# ReadHat_V1_0_0_0.net
KiCad netlist of a schematic drawn in Altium Designer
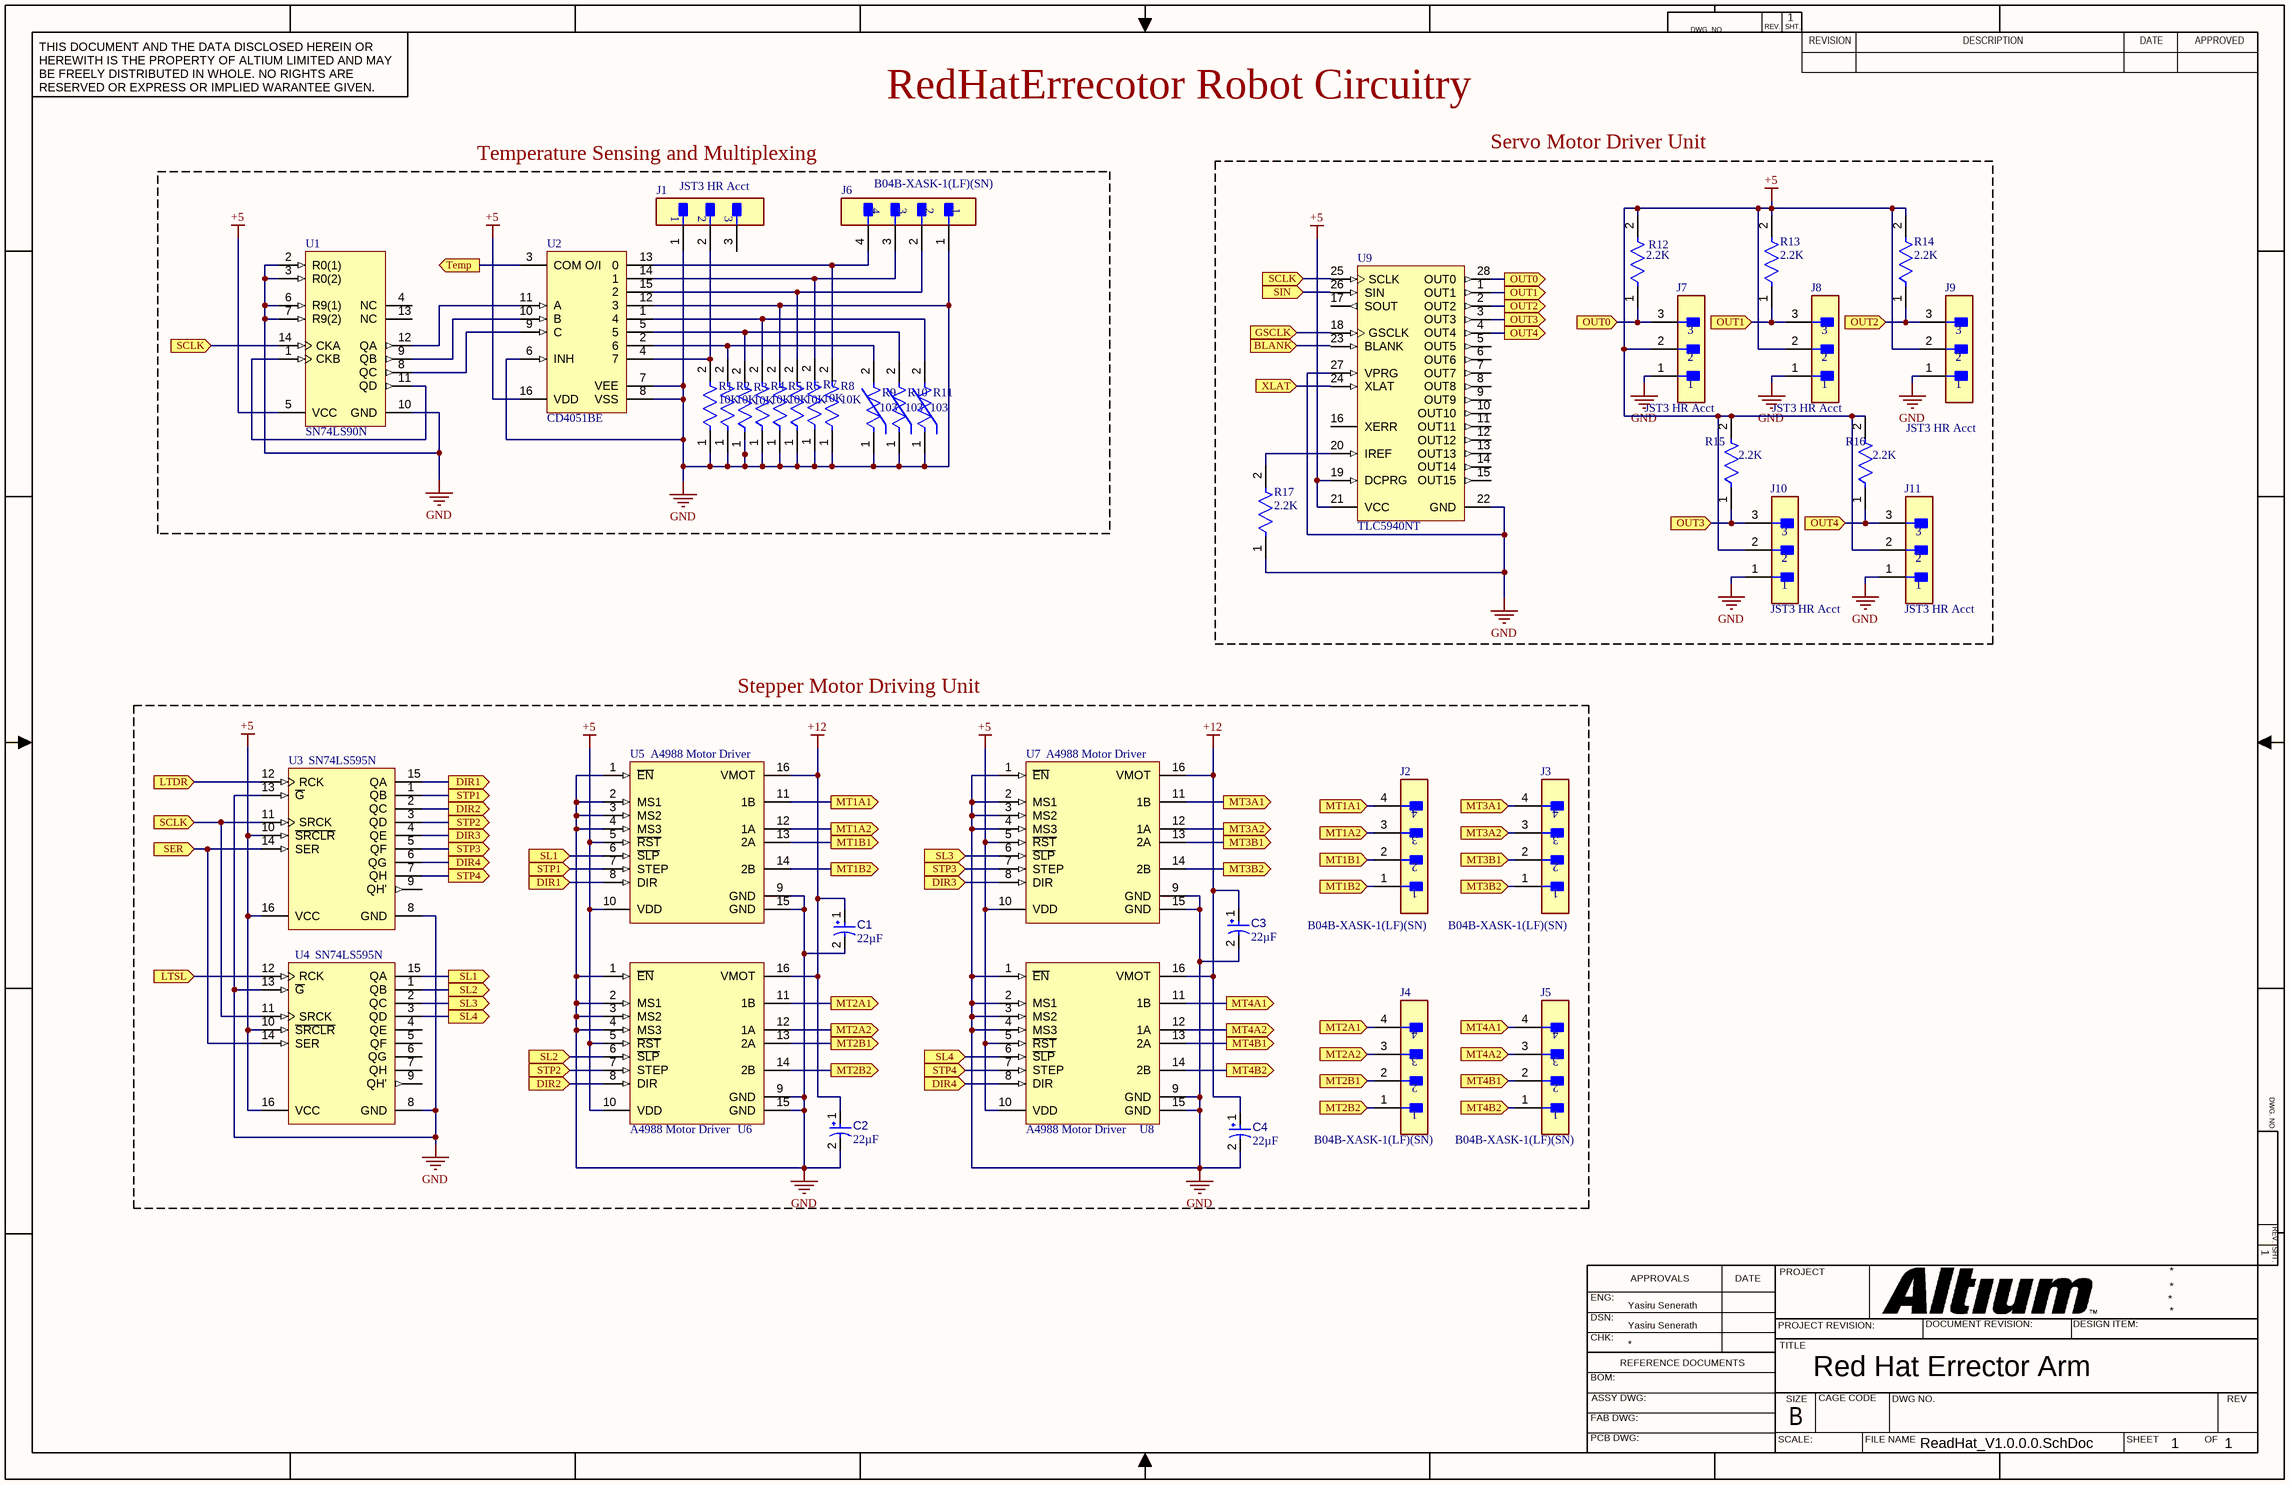
[diagram p0: ReadHat_V1.0.0.0.SchDoc]

(export (version "E")
  (design (tool "Eeschema 10.0.6"))
  (components
    (comp (ref "C1")
      (value "22µF")
      (footprint "CAPPR55-200-1100X500X1200")
      (description "Aluminum Electrolytic Capacitor, 22 uF, +/- 20%, 50 V, -40 to 85 degC, 2-Pin THD, RoHS, Bulk")
      (fields (field (name "MANUFACTURER") "Panasonic") (field (name "TOLERANCE") "20%"))
      (libsource (lib "University of Moratuwa") (part "CAP-P-2"))
    )
    (comp (ref "C2")
      (value "22µF")
      (footprint "CAPPR55-200-1100X500X1200")
      (description "Aluminum Electrolytic Capacitor, 22 uF, +/- 20%, 50 V, -40 to 85 degC, 2-Pin THD, RoHS, Bulk")
      (fields (field (name "MANUFACTURER") "Panasonic") (field (name "TOLERANCE") "20%"))
      (libsource (lib "University of Moratuwa") (part "CAP-P-2"))
    )
    (comp (ref "C3")
      (value "22µF")
      (footprint "CAPPR55-200-1100X500X1200")
      (description "Aluminum Electrolytic Capacitor, 22 uF, +/- 20%, 50 V, -40 to 85 degC, 2-Pin THD, RoHS, Bulk")
      (fields (field (name "MANUFACTURER") "Panasonic") (field (name "TOLERANCE") "20%"))
      (libsource (lib "University of Moratuwa") (part "CAP-P-2"))
    )
    (comp (ref "C4")
      (value "22µF")
      (footprint "CAPPR55-200-1100X500X1200")
      (description "Aluminum Electrolytic Capacitor, 22 uF, +/- 20%, 50 V, -40 to 85 degC, 2-Pin THD, RoHS, Bulk")
      (fields (field (name "MANUFACTURER") "Panasonic") (field (name "TOLERANCE") "20%"))
      (libsource (lib "University of Moratuwa") (part "CAP-P-2"))
    )
    (comp (ref "J1")
      (value "JST3 HR Acct")
      (footprint "FP-B3B-XH-A_LF_SN-MFG")
      (description "CONN HEADER VERT 3POS 2.5MM")
      (libsource (lib "Altium Content Vault") (part "0d3f023dd272f625e17a2be33dea85f"))
    )
    (comp (ref "J2")
      (value "B04B-XASK-1(LF)(SN)")
      (footprint "FP-B04B-XASK-1_LF_SN-MFG")
      (description "CONN HEADER VERT 4POS 2.5MM")
      (fields
        (field (name "OCTOPART") "https://octopart.com/b04b-xask-1%28lf%29%28sn%29-jst-3990149")
        (field (name "MANUFACTURER") "JST")
      )
      (libsource (lib "Altium Content Vault") (part "299a8cea1bdcbc3624fe62c390fa72c"))
    )
    (comp (ref "J3")
      (value "B04B-XASK-1(LF)(SN)")
      (footprint "FP-B04B-XASK-1_LF_SN-MFG")
      (description "CONN HEADER VERT 4POS 2.5MM")
      (fields
        (field (name "OCTOPART") "https://octopart.com/b04b-xask-1%28lf%29%28sn%29-jst-3990149")
        (field (name "MANUFACTURER") "JST")
      )
      (libsource (lib "Altium Content Vault") (part "299a8cea1bdcbc3624fe62c390fa72c"))
    )
    (comp (ref "J4")
      (value "B04B-XASK-1(LF)(SN)")
      (footprint "FP-B04B-XASK-1_LF_SN-MFG")
      (description "CONN HEADER VERT 4POS 2.5MM")
      (fields
        (field (name "OCTOPART") "https://octopart.com/b04b-xask-1%28lf%29%28sn%29-jst-3990149")
        (field (name "MANUFACTURER") "JST")
      )
      (libsource (lib "Altium Content Vault") (part "299a8cea1bdcbc3624fe62c390fa72c"))
    )
    (comp (ref "J5")
      (value "B04B-XASK-1(LF)(SN)")
      (footprint "FP-B04B-XASK-1_LF_SN-MFG")
      (description "CONN HEADER VERT 4POS 2.5MM")
      (fields
        (field (name "OCTOPART") "https://octopart.com/b04b-xask-1%28lf%29%28sn%29-jst-3990149")
        (field (name "MANUFACTURER") "JST")
      )
      (libsource (lib "Altium Content Vault") (part "299a8cea1bdcbc3624fe62c390fa72c"))
    )
    (comp (ref "J6")
      (value "B04B-XASK-1(LF)(SN)")
      (footprint "FP-B04B-XASK-1_LF_SN-MFG")
      (description "CONN HEADER VERT 4POS 2.5MM")
      (fields
        (field (name "OCTOPART") "https://octopart.com/b04b-xask-1%28lf%29%28sn%29-jst-3990149")
        (field (name "MANUFACTURER") "JST")
      )
      (libsource (lib "") (part "299a8cea1bdcbc3624fe62c390fa72c_1"))
    )
    (comp (ref "J7")
      (value "JST3 HR Acct")
      (footprint "FP-B3B-XH-A_LF_SN-MFG")
      (description "CONN HEADER VERT 3POS 2.5MM")
      (libsource (lib "Altium Content Vault") (part "0d3f023dd272f625e17a2be33dea85f"))
    )
    (comp (ref "J8")
      (value "JST3 HR Acct")
      (footprint "FP-B3B-XH-A_LF_SN-MFG")
      (description "CONN HEADER VERT 3POS 2.5MM")
      (libsource (lib "Altium Content Vault") (part "0d3f023dd272f625e17a2be33dea85f"))
    )
    (comp (ref "J9")
      (value "JST3 HR Acct")
      (footprint "FP-B3B-XH-A_LF_SN-MFG")
      (description "CONN HEADER VERT 3POS 2.5MM")
      (libsource (lib "Altium Content Vault") (part "0d3f023dd272f625e17a2be33dea85f"))
    )
    (comp (ref "J10")
      (value "JST3 HR Acct")
      (footprint "FP-B3B-XH-A_LF_SN-MFG")
      (description "CONN HEADER VERT 3POS 2.5MM")
      (libsource (lib "Altium Content Vault") (part "0d3f023dd272f625e17a2be33dea85f"))
    )
    (comp (ref "J11")
      (value "JST3 HR Acct")
      (footprint "FP-B3B-XH-A_LF_SN-MFG")
      (description "CONN HEADER VERT 3POS 2.5MM")
      (libsource (lib "Altium Content Vault") (part "0d3f023dd272f625e17a2be33dea85f"))
    )
    (comp (ref "R1")
      (value "10K")
      (footprint "FP-RNC55-MFG")
      (description "RES 10K OHM 1/8W 1% AXIAL")
      (fields (field (name "TOLERANCE") "1%") (field (name "MANUFACTURER PART NUMBER") "RNC55H1002FSB14"))
      (libsource (lib "Altium Content Vault") (part "1029c3af85768c4190bb7ad29bc67b5"))
    )
    (comp (ref "R2")
      (value "10K")
      (footprint "FP-RNC55-MFG")
      (description "RES 10K OHM 1/8W 1% AXIAL")
      (fields (field (name "TOLERANCE") "1%") (field (name "MANUFACTURER PART NUMBER") "RNC55H1002FSB14"))
      (libsource (lib "Altium Content Vault") (part "1029c3af85768c4190bb7ad29bc67b5"))
    )
    (comp (ref "R3")
      (value "10K")
      (footprint "FP-RNC55-MFG")
      (description "RES 10K OHM 1/8W 1% AXIAL")
      (fields (field (name "TOLERANCE") "1%") (field (name "MANUFACTURER PART NUMBER") "RNC55H1002FSB14"))
      (libsource (lib "Altium Content Vault") (part "1029c3af85768c4190bb7ad29bc67b5"))
    )
    (comp (ref "R4")
      (value "10K")
      (footprint "FP-RNC55-MFG")
      (description "RES 10K OHM 1/8W 1% AXIAL")
      (fields (field (name "TOLERANCE") "1%") (field (name "MANUFACTURER PART NUMBER") "RNC55H1002FSB14"))
      (libsource (lib "Altium Content Vault") (part "1029c3af85768c4190bb7ad29bc67b5"))
    )
    (comp (ref "R5")
      (value "10K")
      (footprint "FP-RNC55-MFG")
      (description "RES 10K OHM 1/8W 1% AXIAL")
      (fields (field (name "TOLERANCE") "1%") (field (name "MANUFACTURER PART NUMBER") "RNC55H1002FSB14"))
      (libsource (lib "Altium Content Vault") (part "1029c3af85768c4190bb7ad29bc67b5"))
    )
    (comp (ref "R6")
      (value "10K")
      (footprint "FP-RNC55-MFG")
      (description "RES 10K OHM 1/8W 1% AXIAL")
      (fields (field (name "TOLERANCE") "1%") (field (name "MANUFACTURER PART NUMBER") "RNC55H1002FSB14"))
      (libsource (lib "Altium Content Vault") (part "1029c3af85768c4190bb7ad29bc67b5"))
    )
    (comp (ref "R7")
      (value "10K")
      (footprint "FP-RNC55-MFG")
      (description "RES 10K OHM 1/8W 1% AXIAL")
      (fields (field (name "TOLERANCE") "1%") (field (name "MANUFACTURER PART NUMBER") "RNC55H1002FSB14"))
      (libsource (lib "Altium Content Vault") (part "1029c3af85768c4190bb7ad29bc67b5"))
    )
    (comp (ref "R8")
      (value "10K")
      (footprint "FP-RNC55-MFG")
      (description "RES 10K OHM 1/8W 1% AXIAL")
      (fields (field (name "TOLERANCE") "1%") (field (name "MANUFACTURER PART NUMBER") "RNC55H1002FSB14"))
      (libsource (lib "Altium Content Vault") (part "1029c3af85768c4190bb7ad29bc67b5"))
    )
    (comp (ref "R9")
      (value "103")
      (footprint "FP-PTFL04_2N34-MFG")
      (description "THERMISTOR PTC 100 OHM DISC")
      (fields (field (name "VOLTAGE") "16V"))
      (libsource (lib "Altium Content Vault") (part "3b148a6ebabc5fb4d708a66c052d352"))
    )
    (comp (ref "R10")
      (value "103")
      (footprint "FP-PTFL04_2N34-MFG")
      (description "THERMISTOR PTC 100 OHM DISC")
      (fields (field (name "VOLTAGE") "16V"))
      (libsource (lib "Altium Content Vault") (part "3b148a6ebabc5fb4d708a66c052d352"))
    )
    (comp (ref "R11")
      (value "103")
      (footprint "FP-PTFL04_2N34-MFG")
      (description "THERMISTOR PTC 100 OHM DISC")
      (fields (field (name "VOLTAGE") "16V"))
      (libsource (lib "Altium Content Vault") (part "3b148a6ebabc5fb4d708a66c052d352"))
    )
    (comp (ref "R12")
      (value "2.2K")
      (footprint "FP-RNC55-MFG")
      (description "RES 5K OHM 1/8W 1% AXIAL")
      (fields (field (name "TOLERANCE") "1%") (field (name "MANUFACTURER PART NUMBER") "RNC55H1002FSB14"))
      (libsource (lib "Altium Content Vault") (part "1029c3af85768c4190bb7ad29bc67b5"))
    )
    (comp (ref "R13")
      (value "2.2K")
      (footprint "FP-RNC55-MFG")
      (description "RES 10K OHM 1/8W 1% AXIAL")
      (fields (field (name "TOLERANCE") "1%") (field (name "MANUFACTURER PART NUMBER") "RNC55H1002FSB14"))
      (libsource (lib "Altium Content Vault") (part "1029c3af85768c4190bb7ad29bc67b5"))
    )
    (comp (ref "R14")
      (value "2.2K")
      (footprint "FP-RNC55-MFG")
      (description "RES 10K OHM 1/8W 1% AXIAL")
      (fields (field (name "TOLERANCE") "1%") (field (name "MANUFACTURER PART NUMBER") "RNC55H1002FSB14"))
      (libsource (lib "Altium Content Vault") (part "1029c3af85768c4190bb7ad29bc67b5"))
    )
    (comp (ref "R15")
      (value "2.2K")
      (footprint "FP-RNC55-MFG")
      (description "RES 10K OHM 1/8W 1% AXIAL")
      (fields (field (name "TOLERANCE") "1%") (field (name "MANUFACTURER PART NUMBER") "RNC55H1002FSB14"))
      (libsource (lib "Altium Content Vault") (part "1029c3af85768c4190bb7ad29bc67b5"))
    )
    (comp (ref "R16")
      (value "2.2K")
      (footprint "FP-RNC55-MFG")
      (description "RES 10K OHM 1/8W 1% AXIAL")
      (fields (field (name "TOLERANCE") "1%") (field (name "MANUFACTURER PART NUMBER") "RNC55H1002FSB14"))
      (libsource (lib "Altium Content Vault") (part "1029c3af85768c4190bb7ad29bc67b5"))
    )
    (comp (ref "R17")
      (value "2.2K")
      (footprint "FP-RNC55-MFG")
      (description "RES 10K OHM 1/8W 1% AXIAL")
      (fields (field (name "TOLERANCE") "1%") (field (name "MANUFACTURER PART NUMBER") "RNC55H1002FSB14"))
      (libsource (lib "Altium Content Vault") (part "1029c3af85768c4190bb7ad29bc67b5"))
    )
    (comp (ref "U1")
      (value "SN74LS90N")
      (footprint "N0014A")
      (description "Decade Counter, N0014A, TUBE")
      (fields
        (field (name "GENERIC PART NUMBER") "SN74LS90")
        (field (name "MANUFACTURER") "Texas Instruments")
      )
      (libsource (lib "Altium Content Vault") (part "TI-SNX4LS90-14"))
    )
    (comp (ref "U2")
      (value "CD4051BE")
      (footprint "N0016A")
      (description "CMOS Single 8-Channel Analog Multiplexer/Demultiplexer with Logic-Level Conversion, N0016A, TUBE")
      (fields
        (field (name "GENERIC PART NUMBER") "CD4051B")
        (field (name "MANUFACTURER") "Texas Instruments")
      )
      (libsource (lib "Altium Content Vault") (part "TI-CD4051B-16"))
    )
    (comp (ref "U3")
      (value "SN74LS595N")
      (footprint "N0016A")
      (description "Serial-in shift registers with output registers, N0016A, TUBE")
      (fields
        (field (name "GENERIC PART NUMBER") "SN74LS595")
        (field (name "MANUFACTURER") "Texas Instruments")
      )
      (libsource (lib "Altium Content Vault") (part "TI-SN74LS595-16"))
    )
    (comp (ref "U4")
      (value "SN74LS595N")
      (footprint "N0016A")
      (description "Serial-in shift registers with output registers, N0016A, TUBE")
      (fields
        (field (name "GENERIC PART NUMBER") "SN74LS595")
        (field (name "MANUFACTURER") "Texas Instruments")
      )
      (libsource (lib "Altium Content Vault") (part "TI-SN74LS595-16"))
    )
    (comp (ref "U5")
      (value "A4988 Motor Driver")
      (footprint "Polo-A4988 Motor Driver_V")
      (description "Stepper Motor Driver Carrier, 3 to 5.5 V, 2 A, 16-Pin THD")
      (fields (field (name "MANUFACTURER") "Pololu Robotics & Electronics"))
      (libsource (lib "University of Moratuwa") (part "POLO-A4988-16"))
    )
    (comp (ref "U6")
      (value "A4988 Motor Driver")
      (footprint "Polo-A4988 Motor Driver_V")
      (description "Stepper Motor Driver Carrier, 3 to 5.5 V, 2 A, 16-Pin THD")
      (fields (field (name "MANUFACTURER") "Pololu Robotics & Electronics"))
      (libsource (lib "University of Moratuwa") (part "POLO-A4988-16"))
    )
    (comp (ref "U7")
      (value "A4988 Motor Driver")
      (footprint "Polo-A4988 Motor Driver_V")
      (description "Stepper Motor Driver Carrier, 3 to 5.5 V, 2 A, 16-Pin THD")
      (fields (field (name "MANUFACTURER") "Pololu Robotics & Electronics"))
      (libsource (lib "University of Moratuwa") (part "POLO-A4988-16"))
    )
    (comp (ref "U8")
      (value "A4988 Motor Driver")
      (footprint "Polo-A4988 Motor Driver_V")
      (description "Stepper Motor Driver Carrier, 3 to 5.5 V, 2 A, 16-Pin THD")
      (fields (field (name "MANUFACTURER") "Pololu Robotics & Electronics"))
      (libsource (lib "University of Moratuwa") (part "POLO-A4988-16"))
    )
    (comp (ref "U9")
      (value "TLC5940NT")
      (footprint "NT0028A")
      (fields (field (name "MANUFACTURER") "Texas Instruments"))
      (libsource (lib "Altium Content Vault") (part "TI-TLC5940NT28"))
    )
  )
  (nets
    (net (code "1") (name "+5") (class "Default")
      (node (ref "J10") (pin "2") (pinfunction "2_2") (pintype "passive"))
      (node (ref "J11") (pin "2") (pinfunction "2_2") (pintype "passive"))
      (node (ref "J7") (pin "2") (pinfunction "2_2") (pintype "passive"))
      (node (ref "J8") (pin "2") (pinfunction "2_2") (pintype "passive"))
      (node (ref "J9") (pin "2") (pinfunction "2_2") (pintype "passive"))
      (node (ref "R12") (pin "2") (pinfunction "2_2") (pintype "passive"))
      (node (ref "R13") (pin "2") (pinfunction "2_2") (pintype "passive"))
      (node (ref "R14") (pin "2") (pinfunction "2_2") (pintype "passive"))
      (node (ref "R15") (pin "2") (pinfunction "2_2") (pintype "passive"))
      (node (ref "R16") (pin "2") (pinfunction "2_2") (pintype "passive"))
      (node (ref "U1") (pin "5") (pinfunction "VCC_5") (pintype "power_in"))
      (node (ref "U2") (pin "16") (pinfunction "VDD_16") (pintype "power_in"))
      (node (ref "U3") (pin "10") (pinfunction "~{SRCLR}_10") (pintype "input"))
      (node (ref "U3") (pin "16") (pinfunction "VCC_16") (pintype "power_in"))
      (node (ref "U4") (pin "10") (pinfunction "~{SRCLR}_10") (pintype "input"))
      (node (ref "U4") (pin "16") (pinfunction "VCC_16") (pintype "power_in"))
      (node (ref "U5") (pin "10") (pinfunction "VDD_10") (pintype "power_in"))
      (node (ref "U5") (pin "5") (pinfunction "~{RST}_5") (pintype "input"))
      (node (ref "U6") (pin "10") (pinfunction "VDD_10") (pintype "power_in"))
      (node (ref "U6") (pin "5") (pinfunction "~{RST}_5") (pintype "input"))
      (node (ref "U7") (pin "10") (pinfunction "VDD_10") (pintype "power_in"))
      (node (ref "U7") (pin "5") (pinfunction "~{RST}_5") (pintype "input"))
      (node (ref "U8") (pin "10") (pinfunction "VDD_10") (pintype "power_in"))
      (node (ref "U8") (pin "5") (pinfunction "~{RST}_5") (pintype "input"))
      (node (ref "U9") (pin "19") (pinfunction "DCPRG_19") (pintype "input"))
      (node (ref "U9") (pin "21") (pinfunction "VCC_21") (pintype "power_in"))
    )
    (net (code "2") (name "+12") (class "Default")
      (node (ref "C1") (pin "1") (pinfunction "1_1") (pintype "passive"))
      (node (ref "C2") (pin "1") (pinfunction "1_1") (pintype "passive"))
      (node (ref "C3") (pin "1") (pinfunction "1_1") (pintype "passive"))
      (node (ref "C4") (pin "1") (pinfunction "1_1") (pintype "passive"))
      (node (ref "U5") (pin "16") (pinfunction "VMOT_16") (pintype "power_in"))
      (node (ref "U6") (pin "16") (pinfunction "VMOT_16") (pintype "power_in"))
      (node (ref "U7") (pin "16") (pinfunction "VMOT_16") (pintype "power_in"))
      (node (ref "U8") (pin "16") (pinfunction "VMOT_16") (pintype "power_in"))
    )
    (net (code "4") (name "/DIR1") (class "Default")
      (node (ref "U3") (pin "15") (pinfunction "QA_15") (pintype "tri_state"))
      (node (ref "U5") (pin "8") (pinfunction "DIR_8") (pintype "input"))
    )
    (net (code "5") (name "/DIR2") (class "Default")
      (node (ref "U3") (pin "2") (pinfunction "QC_2") (pintype "tri_state"))
      (node (ref "U6") (pin "8") (pinfunction "DIR_8") (pintype "input"))
    )
    (net (code "6") (name "/DIR3") (class "Default")
      (node (ref "U3") (pin "4") (pinfunction "QE_4") (pintype "tri_state"))
      (node (ref "U7") (pin "8") (pinfunction "DIR_8") (pintype "input"))
    )
    (net (code "7") (name "/DIR4") (class "Default")
      (node (ref "U3") (pin "6") (pinfunction "QG_6") (pintype "tri_state"))
      (node (ref "U8") (pin "8") (pinfunction "DIR_8") (pintype "input"))
    )
    (net (code "8") (name "/GSCLK") (class "Default")
      (node (ref "U9") (pin "18") (pinfunction "GSCLK_18") (pintype "input"))
    )
    (net (code "9") (name "/LTDR") (class "Default")
      (node (ref "U3") (pin "12") (pinfunction "RCK_12") (pintype "input"))
    )
    (net (code "10") (name "/LTSL") (class "Default")
      (node (ref "U4") (pin "12") (pinfunction "RCK_12") (pintype "input"))
    )
    (net (code "11") (name "/MT1A1") (class "Default")
      (node (ref "J2") (pin "4") (pinfunction "4_4") (pintype "passive"))
      (node (ref "U5") (pin "11") (pinfunction "1B_11") (pintype "power_in"))
    )
    (net (code "12") (name "/MT1A2") (class "Default")
      (node (ref "J2") (pin "3") (pinfunction "3_3") (pintype "passive"))
      (node (ref "U5") (pin "12") (pinfunction "1A_12") (pintype "power_in"))
    )
    (net (code "13") (name "/MT1B1") (class "Default")
      (node (ref "J2") (pin "2") (pinfunction "2_2") (pintype "passive"))
      (node (ref "U5") (pin "13") (pinfunction "2A_13") (pintype "power_in"))
    )
    (net (code "14") (name "/MT1B2") (class "Default")
      (node (ref "J2") (pin "1") (pinfunction "1_1") (pintype "passive"))
      (node (ref "U5") (pin "14") (pinfunction "2B_14") (pintype "power_in"))
    )
    (net (code "15") (name "/MT2A1") (class "Default")
      (node (ref "J4") (pin "4") (pinfunction "4_4") (pintype "passive"))
      (node (ref "U6") (pin "11") (pinfunction "1B_11") (pintype "power_in"))
    )
    (net (code "16") (name "/MT2A2") (class "Default")
      (node (ref "J4") (pin "3") (pinfunction "3_3") (pintype "passive"))
      (node (ref "U6") (pin "12") (pinfunction "1A_12") (pintype "power_in"))
    )
    (net (code "17") (name "/MT2B1") (class "Default")
      (node (ref "J4") (pin "2") (pinfunction "2_2") (pintype "passive"))
      (node (ref "U6") (pin "13") (pinfunction "2A_13") (pintype "power_in"))
    )
    (net (code "18") (name "/MT2B2") (class "Default")
      (node (ref "J4") (pin "1") (pinfunction "1_1") (pintype "passive"))
      (node (ref "U6") (pin "14") (pinfunction "2B_14") (pintype "power_in"))
    )
    (net (code "19") (name "/MT3A1") (class "Default")
      (node (ref "J3") (pin "4") (pinfunction "4_4") (pintype "passive"))
      (node (ref "U7") (pin "11") (pinfunction "1B_11") (pintype "power_in"))
    )
    (net (code "20") (name "/MT3A2") (class "Default")
      (node (ref "J3") (pin "3") (pinfunction "3_3") (pintype "passive"))
      (node (ref "U7") (pin "12") (pinfunction "1A_12") (pintype "power_in"))
    )
    (net (code "21") (name "/MT3B1") (class "Default")
      (node (ref "J3") (pin "2") (pinfunction "2_2") (pintype "passive"))
      (node (ref "U7") (pin "13") (pinfunction "2A_13") (pintype "power_in"))
    )
    (net (code "22") (name "/MT3B2") (class "Default")
      (node (ref "J3") (pin "1") (pinfunction "1_1") (pintype "passive"))
      (node (ref "U7") (pin "14") (pinfunction "2B_14") (pintype "power_in"))
    )
    (net (code "23") (name "/MT4A1") (class "Default")
      (node (ref "J5") (pin "4") (pinfunction "4_4") (pintype "passive"))
      (node (ref "U8") (pin "11") (pinfunction "1B_11") (pintype "power_in"))
    )
    (net (code "24") (name "/MT4A2") (class "Default")
      (node (ref "J5") (pin "3") (pinfunction "3_3") (pintype "passive"))
      (node (ref "U8") (pin "12") (pinfunction "1A_12") (pintype "power_in"))
    )
    (net (code "25") (name "/MT4B1") (class "Default")
      (node (ref "J5") (pin "2") (pinfunction "2_2") (pintype "passive"))
      (node (ref "U8") (pin "13") (pinfunction "2A_13") (pintype "power_in"))
    )
    (net (code "26") (name "/MT4B2") (class "Default")
      (node (ref "J5") (pin "1") (pinfunction "1_1") (pintype "passive"))
      (node (ref "U8") (pin "14") (pinfunction "2B_14") (pintype "power_in"))
    )
    (net (code "27") (name "/OUT0") (class "Default")
      (node (ref "J7") (pin "3") (pinfunction "3_3") (pintype "passive"))
      (node (ref "R12") (pin "1") (pinfunction "1_1") (pintype "passive"))
      (node (ref "U9") (pin "28") (pinfunction "OUT0_28") (pintype "output"))
    )
    (net (code "28") (name "/OUT1") (class "Default")
      (node (ref "J8") (pin "3") (pinfunction "3_3") (pintype "passive"))
      (node (ref "R13") (pin "1") (pinfunction "1_1") (pintype "passive"))
      (node (ref "U9") (pin "1") (pinfunction "OUT1_1") (pintype "output"))
    )
    (net (code "29") (name "/OUT2") (class "Default")
      (node (ref "J9") (pin "3") (pinfunction "3_3") (pintype "passive"))
      (node (ref "R14") (pin "1") (pinfunction "1_1") (pintype "passive"))
      (node (ref "U9") (pin "2") (pinfunction "OUT2_2") (pintype "output"))
    )
    (net (code "30") (name "/OUT3") (class "Default")
      (node (ref "J10") (pin "3") (pinfunction "3_3") (pintype "passive"))
      (node (ref "R15") (pin "1") (pinfunction "1_1") (pintype "passive"))
      (node (ref "U9") (pin "3") (pinfunction "OUT3_3") (pintype "output"))
    )
    (net (code "31") (name "/OUT4") (class "Default")
      (node (ref "J11") (pin "3") (pinfunction "3_3") (pintype "passive"))
      (node (ref "R16") (pin "1") (pinfunction "1_1") (pintype "passive"))
      (node (ref "U9") (pin "4") (pinfunction "OUT4_4") (pintype "output"))
    )
    (net (code "32") (name "/SCLK") (class "Default")
      (node (ref "U1") (pin "14") (pinfunction "CKA_14") (pintype "input"))
      (node (ref "U3") (pin "11") (pinfunction "SRCK_11") (pintype "input"))
      (node (ref "U4") (pin "11") (pinfunction "SRCK_11") (pintype "input"))
      (node (ref "U9") (pin "25") (pinfunction "SCLK_25") (pintype "input"))
    )
    (net (code "33") (name "/SER") (class "Default")
      (node (ref "U3") (pin "14") (pinfunction "SER_14") (pintype "input"))
      (node (ref "U4") (pin "14") (pinfunction "SER_14") (pintype "input"))
    )
    (net (code "35") (name "/SL1") (class "Default")
      (node (ref "U4") (pin "15") (pinfunction "QA_15") (pintype "tri_state"))
      (node (ref "U5") (pin "6") (pinfunction "~{SLP}_6") (pintype "input"))
    )
    (net (code "36") (name "/SL2") (class "Default")
      (node (ref "U4") (pin "1") (pinfunction "QB_1") (pintype "tri_state"))
      (node (ref "U6") (pin "6") (pinfunction "~{SLP}_6") (pintype "input"))
    )
    (net (code "37") (name "/SL3") (class "Default")
      (node (ref "U4") (pin "2") (pinfunction "QC_2") (pintype "tri_state"))
      (node (ref "U7") (pin "6") (pinfunction "~{SLP}_6") (pintype "input"))
    )
    (net (code "38") (name "/SL4") (class "Default")
      (node (ref "U4") (pin "3") (pinfunction "QD_3") (pintype "tri_state"))
      (node (ref "U8") (pin "6") (pinfunction "~{SLP}_6") (pintype "input"))
    )
    (net (code "39") (name "/STP1") (class "Default")
      (node (ref "U3") (pin "1") (pinfunction "QB_1") (pintype "tri_state"))
      (node (ref "U5") (pin "7") (pinfunction "STEP_7") (pintype "input"))
    )
    (net (code "40") (name "/STP2") (class "Default")
      (node (ref "U3") (pin "3") (pinfunction "QD_3") (pintype "tri_state"))
      (node (ref "U6") (pin "7") (pinfunction "STEP_7") (pintype "input"))
    )
    (net (code "41") (name "/STP3") (class "Default")
      (node (ref "U3") (pin "5") (pinfunction "QF_5") (pintype "tri_state"))
      (node (ref "U7") (pin "7") (pinfunction "STEP_7") (pintype "input"))
    )
    (net (code "42") (name "/STP4") (class "Default")
      (node (ref "U3") (pin "7") (pinfunction "QH_7") (pintype "tri_state"))
      (node (ref "U8") (pin "7") (pinfunction "STEP_7") (pintype "input"))
    )
    (net (code "43") (name "/Temp") (class "Default")
      (node (ref "U2") (pin "3") (pinfunction "COM_O/I_3") (pintype "passive"))
    )
    (net (code "44") (name "/XLAT") (class "Default")
      (node (ref "U9") (pin "24") (pinfunction "XLAT_24") (pintype "input"))
    )
    (net (code "45") (name "GND") (class "Default")
      (node (ref "C1") (pin "2") (pinfunction "2_2") (pintype "passive"))
      (node (ref "C2") (pin "2") (pinfunction "2_2") (pintype "passive"))
      (node (ref "C3") (pin "2") (pinfunction "2_2") (pintype "passive"))
      (node (ref "C4") (pin "2") (pinfunction "2_2") (pintype "passive"))
      (node (ref "J1") (pin "1") (pinfunction "1_1") (pintype "passive"))
      (node (ref "J10") (pin "1") (pinfunction "1_1") (pintype "passive"))
      (node (ref "J11") (pin "1") (pinfunction "1_1") (pintype "passive"))
      (node (ref "J6") (pin "1") (pinfunction "1_1") (pintype "passive"))
      (node (ref "J7") (pin "1") (pinfunction "1_1") (pintype "passive"))
      (node (ref "J8") (pin "1") (pinfunction "1_1") (pintype "passive"))
      (node (ref "J9") (pin "1") (pinfunction "1_1") (pintype "passive"))
      (node (ref "R1") (pin "1") (pinfunction "1_1") (pintype "passive"))
      (node (ref "R10") (pin "1") (pinfunction "1_1") (pintype "passive"))
      (node (ref "R11") (pin "1") (pinfunction "1_1") (pintype "passive"))
      (node (ref "R17") (pin "1") (pinfunction "1_1") (pintype "passive"))
      (node (ref "R2") (pin "1") (pinfunction "1_1") (pintype "passive"))
      (node (ref "R3") (pin "1") (pinfunction "1_1") (pintype "passive"))
      (node (ref "R4") (pin "1") (pinfunction "1_1") (pintype "passive"))
      (node (ref "R5") (pin "1") (pinfunction "1_1") (pintype "passive"))
      (node (ref "R5") (pin "2") (pinfunction "2_2") (pintype "passive"))
      (node (ref "R6") (pin "1") (pinfunction "1_1") (pintype "passive"))
      (node (ref "R7") (pin "1") (pinfunction "1_1") (pintype "passive"))
      (node (ref "R8") (pin "1") (pinfunction "1_1") (pintype "passive"))
      (node (ref "R9") (pin "1") (pinfunction "1_1") (pintype "passive"))
      (node (ref "U1") (pin "10") (pinfunction "GND_10") (pintype "power_in"))
      (node (ref "U1") (pin "2") (pinfunction "R0(1)_2") (pintype "input"))
      (node (ref "U1") (pin "3") (pinfunction "R0(2)_3") (pintype "input"))
      (node (ref "U1") (pin "6") (pinfunction "R9(1)_6") (pintype "input"))
      (node (ref "U1") (pin "7") (pinfunction "R9(2)_7") (pintype "input"))
      (node (ref "U2") (pin "12") (pinfunction "3_12") (pintype "passive"))
      (node (ref "U2") (pin "6") (pinfunction "INH_6") (pintype "input"))
      (node (ref "U2") (pin "7") (pinfunction "VEE_7") (pintype "power_in"))
      (node (ref "U2") (pin "8") (pinfunction "VSS_8") (pintype "power_in"))
      (node (ref "U3") (pin "13") (pinfunction "~{G}_13") (pintype "input"))
      (node (ref "U3") (pin "8") (pinfunction "GND_8") (pintype "power_in"))
      (node (ref "U4") (pin "13") (pinfunction "~{G}_13") (pintype "input"))
      (node (ref "U4") (pin "8") (pinfunction "GND_8") (pintype "power_in"))
      (node (ref "U5") (pin "1") (pinfunction "~{EN}_1") (pintype "input"))
      (node (ref "U5") (pin "15") (pinfunction "GND_15") (pintype "power_in"))
      (node (ref "U5") (pin "2") (pinfunction "MS1_2") (pintype "input"))
      (node (ref "U5") (pin "3") (pinfunction "MS2_3") (pintype "input"))
      (node (ref "U5") (pin "4") (pinfunction "MS3_4") (pintype "input"))
      (node (ref "U5") (pin "9") (pinfunction "GND_9") (pintype "power_in"))
      (node (ref "U6") (pin "1") (pinfunction "~{EN}_1") (pintype "input"))
      (node (ref "U6") (pin "15") (pinfunction "GND_15") (pintype "power_in"))
      (node (ref "U6") (pin "2") (pinfunction "MS1_2") (pintype "input"))
      (node (ref "U6") (pin "3") (pinfunction "MS2_3") (pintype "input"))
      (node (ref "U6") (pin "4") (pinfunction "MS3_4") (pintype "input"))
      (node (ref "U6") (pin "9") (pinfunction "GND_9") (pintype "power_in"))
      (node (ref "U7") (pin "1") (pinfunction "~{EN}_1") (pintype "input"))
      (node (ref "U7") (pin "15") (pinfunction "GND_15") (pintype "power_in"))
      (node (ref "U7") (pin "2") (pinfunction "MS1_2") (pintype "input"))
      (node (ref "U7") (pin "3") (pinfunction "MS2_3") (pintype "input"))
      (node (ref "U7") (pin "4") (pinfunction "MS3_4") (pintype "input"))
      (node (ref "U7") (pin "9") (pinfunction "GND_9") (pintype "power_in"))
      (node (ref "U8") (pin "1") (pinfunction "~{EN}_1") (pintype "input"))
      (node (ref "U8") (pin "15") (pinfunction "GND_15") (pintype "power_in"))
      (node (ref "U8") (pin "2") (pinfunction "MS1_2") (pintype "input"))
      (node (ref "U8") (pin "3") (pinfunction "MS2_3") (pintype "input"))
      (node (ref "U8") (pin "4") (pinfunction "MS3_4") (pintype "input"))
      (node (ref "U8") (pin "9") (pinfunction "GND_9") (pintype "power_in"))
      (node (ref "U9") (pin "22") (pinfunction "GND_22") (pintype "power_in"))
      (node (ref "U9") (pin "27") (pinfunction "VPRG_27") (pintype "input"))
    )
    (net (code "46") (name "Net-(R10-Pad2)") (class "Default")
      (node (ref "R10") (pin "2") (pinfunction "2_2") (pintype "passive"))
      (node (ref "R3") (pin "2") (pinfunction "2_2") (pintype "passive"))
      (node (ref "U2") (pin "5") (pinfunction "5_5") (pintype "passive"))
    )
    (net (code "47") (name "Net-(U1-CKB)") (class "Default")
      (node (ref "U1") (pin "1") (pinfunction "CKB_1") (pintype "input"))
      (node (ref "U1") (pin "11") (pinfunction "QD_11") (pintype "output"))
    )
    (net (code "48") (name "Net-(U1-QA)") (class "Default")
      (node (ref "U1") (pin "12") (pinfunction "QA_12") (pintype "output"))
      (node (ref "U2") (pin "11") (pinfunction "A_11") (pintype "input"))
    )
    (net (code "49") (name "Net-(U1-QB)") (class "Default")
      (node (ref "U1") (pin "9") (pinfunction "QB_9") (pintype "output"))
      (node (ref "U2") (pin "10") (pinfunction "B_10") (pintype "input"))
    )
    (net (code "50") (name "Net-(U1-QC)") (class "Default")
      (node (ref "U1") (pin "8") (pinfunction "QC_8") (pintype "output"))
      (node (ref "U2") (pin "9") (pinfunction "C_9") (pintype "input"))
    )
    (net (code "51") (name "Net-(U2-0)") (class "Default")
      (node (ref "J6") (pin "4") (pinfunction "4_4") (pintype "passive"))
      (node (ref "R8") (pin "2") (pinfunction "2_2") (pintype "passive"))
      (node (ref "U2") (pin "13") (pinfunction "0_13") (pintype "passive"))
    )
    (net (code "52") (name "Net-(U2-1)") (class "Default")
      (node (ref "J6") (pin "3") (pinfunction "3_3") (pintype "passive"))
      (node (ref "R7") (pin "2") (pinfunction "2_2") (pintype "passive"))
      (node (ref "U2") (pin "14") (pinfunction "1_14") (pintype "passive"))
    )
    (net (code "53") (name "Net-(U2-2)") (class "Default")
      (node (ref "J6") (pin "2") (pinfunction "2_2") (pintype "passive"))
      (node (ref "R6") (pin "2") (pinfunction "2_2") (pintype "passive"))
      (node (ref "U2") (pin "15") (pinfunction "2_15") (pintype "passive"))
    )
    (net (code "54") (name "Net-(U2-4)") (class "Default")
      (node (ref "R11") (pin "2") (pinfunction "2_2") (pintype "passive"))
      (node (ref "R4") (pin "2") (pinfunction "2_2") (pintype "passive"))
      (node (ref "U2") (pin "1") (pinfunction "4_1") (pintype "passive"))
    )
    (net (code "55") (name "Net-(U2-6)") (class "Default")
      (node (ref "R2") (pin "2") (pinfunction "2_2") (pintype "passive"))
      (node (ref "R9") (pin "2") (pinfunction "2_2") (pintype "passive"))
      (node (ref "U2") (pin "2") (pinfunction "6_2") (pintype "passive"))
    )
    (net (code "56") (name "Net-(U2-7)") (class "Default")
      (node (ref "J1") (pin "2") (pinfunction "2_2") (pintype "passive"))
      (node (ref "R1") (pin "2") (pinfunction "2_2") (pintype "passive"))
      (node (ref "U2") (pin "4") (pinfunction "7_4") (pintype "passive"))
    )
    (net (code "57") (name "Net-(U9-IREF)") (class "Default")
      (node (ref "R17") (pin "2") (pinfunction "2_2") (pintype "passive"))
      (node (ref "U9") (pin "20") (pinfunction "IREF_20") (pintype "input"))
    )
    (net (code "58") (name "unconnected-(J1-Pad3)") (class "Default")
      (node (ref "J1") (pin "3") (pinfunction "3_3") (pintype "passive"))
    )
    (net (code "59") (name "unconnected-(U1-NC-Pad4)") (class "Default")
      (node (ref "U1") (pin "4") (pinfunction "NC_4") (pintype "passive"))
    )
    (net (code "60") (name "unconnected-(U1-NC-Pad13)") (class "Default")
      (node (ref "U1") (pin "13") (pinfunction "NC_13") (pintype "passive"))
    )
    (net (code "61") (name "unconnected-(U3-QH'-Pad9)") (class "Default")
      (node (ref "U3") (pin "9") (pinfunction "QH'_9") (pintype "output"))
    )
    (net (code "62") (name "unconnected-(U4-QE-Pad4)") (class "Default")
      (node (ref "U4") (pin "4") (pinfunction "QE_4") (pintype "tri_state"))
    )
    (net (code "63") (name "unconnected-(U4-QF-Pad5)") (class "Default")
      (node (ref "U4") (pin "5") (pinfunction "QF_5") (pintype "tri_state"))
    )
    (net (code "64") (name "unconnected-(U4-QG-Pad6)") (class "Default")
      (node (ref "U4") (pin "6") (pinfunction "QG_6") (pintype "tri_state"))
    )
    (net (code "65") (name "unconnected-(U4-QH'-Pad9)") (class "Default")
      (node (ref "U4") (pin "9") (pinfunction "QH'_9") (pintype "output"))
    )
    (net (code "66") (name "unconnected-(U4-QH-Pad7)") (class "Default")
      (node (ref "U4") (pin "7") (pinfunction "QH_7") (pintype "tri_state"))
    )
    (net (code "67") (name "unconnected-(U9-BLANK-Pad23)") (class "Default")
      (node (ref "U9") (pin "23") (pinfunction "BLANK_23") (pintype "input"))
    )
    (net (code "68") (name "unconnected-(U9-OUT5-Pad5)") (class "Default")
      (node (ref "U9") (pin "5") (pinfunction "OUT5_5") (pintype "output"))
    )
    (net (code "69") (name "unconnected-(U9-OUT6-Pad6)") (class "Default")
      (node (ref "U9") (pin "6") (pinfunction "OUT6_6") (pintype "output"))
    )
    (net (code "70") (name "unconnected-(U9-OUT7-Pad7)") (class "Default")
      (node (ref "U9") (pin "7") (pinfunction "OUT7_7") (pintype "output"))
    )
    (net (code "71") (name "unconnected-(U9-OUT8-Pad8)") (class "Default")
      (node (ref "U9") (pin "8") (pinfunction "OUT8_8") (pintype "output"))
    )
    (net (code "72") (name "unconnected-(U9-OUT9-Pad9)") (class "Default")
      (node (ref "U9") (pin "9") (pinfunction "OUT9_9") (pintype "output"))
    )
    (net (code "73") (name "unconnected-(U9-OUT10-Pad10)") (class "Default")
      (node (ref "U9") (pin "10") (pinfunction "OUT10_10") (pintype "output"))
    )
    (net (code "74") (name "unconnected-(U9-OUT11-Pad11)") (class "Default")
      (node (ref "U9") (pin "11") (pinfunction "OUT11_11") (pintype "output"))
    )
    (net (code "75") (name "unconnected-(U9-OUT12-Pad12)") (class "Default")
      (node (ref "U9") (pin "12") (pinfunction "OUT12_12") (pintype "output"))
    )
    (net (code "76") (name "unconnected-(U9-OUT13-Pad13)") (class "Default")
      (node (ref "U9") (pin "13") (pinfunction "OUT13_13") (pintype "output"))
    )
    (net (code "77") (name "unconnected-(U9-OUT14-Pad14)") (class "Default")
      (node (ref "U9") (pin "14") (pinfunction "OUT14_14") (pintype "output"))
    )
    (net (code "78") (name "unconnected-(U9-OUT15-Pad15)") (class "Default")
      (node (ref "U9") (pin "15") (pinfunction "OUT15_15") (pintype "output"))
    )
    (net (code "79") (name "unconnected-(U9-SIN-Pad26)") (class "Default")
      (node (ref "U9") (pin "26") (pinfunction "SIN_26") (pintype "input"))
    )
    (net (code "80") (name "unconnected-(U9-SOUT-Pad17)") (class "Default")
      (node (ref "U9") (pin "17") (pinfunction "SOUT_17") (pintype "output"))
    )
    (net (code "81") (name "unconnected-(U9-XERR-Pad16)") (class "Default")
      (node (ref "U9") (pin "16") (pinfunction "XERR_16") (pintype "tri_state"))
    )
  )
)
